# B4L_power.net
KiCad netlist of a schematic drawn in EAGLE
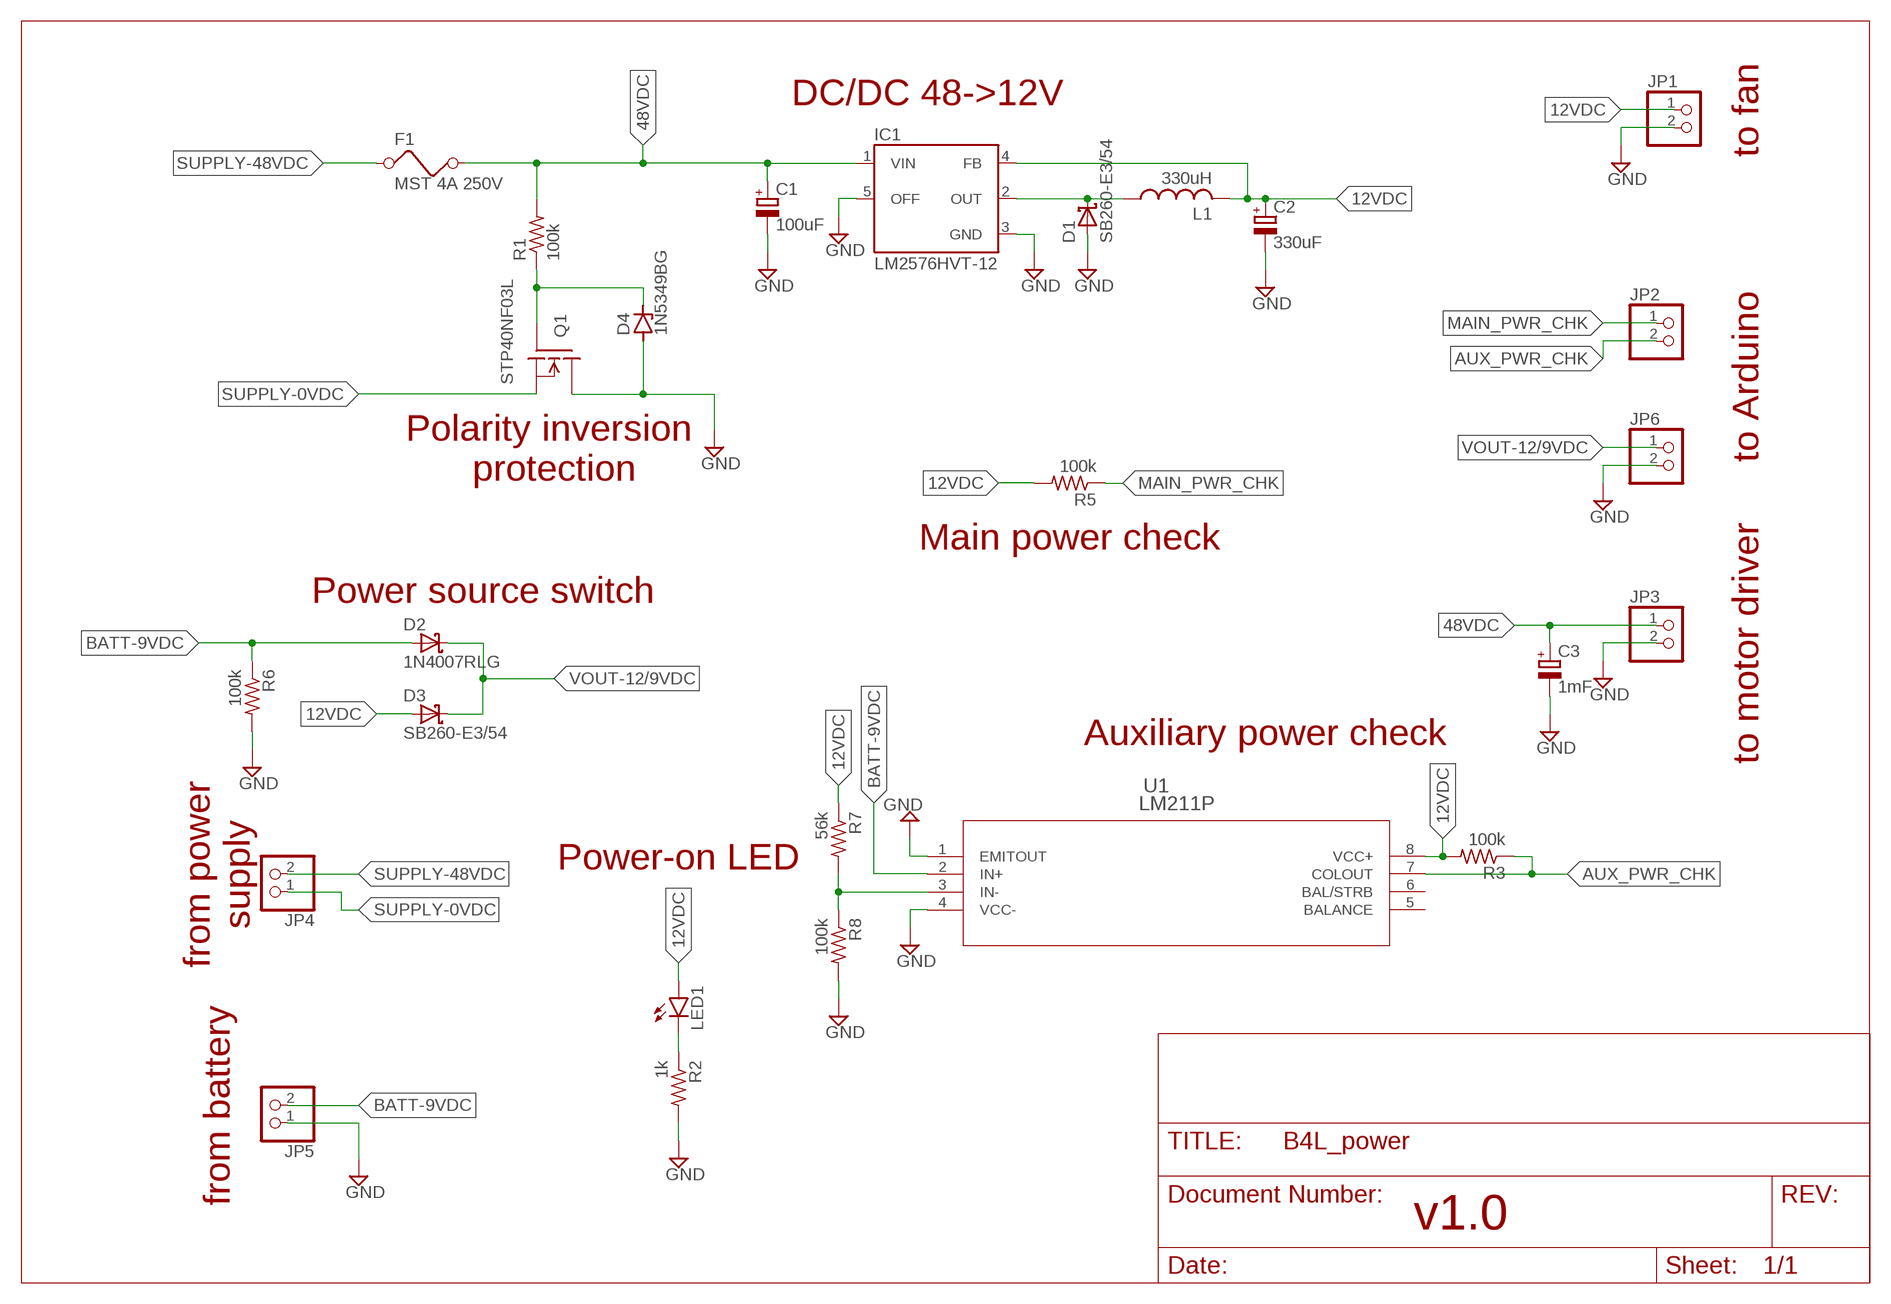
[diagram p0: schematic, sheet 1]

(export (version "E")
  (design (tool "Eeschema 10.0.6"))
  (components
    (comp (ref "C1")
      (value "100uF")
      (footprint "eagle-import:140CLH-1010")
      (libsource (lib "eagle-import") (part "CPOL-EU140CLH-1010"))
    )
    (comp (ref "C2")
      (value "330uF")
      (footprint "eagle-import:140CLH-1010")
      (libsource (lib "eagle-import") (part "CPOL-EU140CLH-1010"))
    )
    (comp (ref "C3")
      (value "1mF")
      (footprint "eagle-import:140CLH-1010")
      (libsource (lib "eagle-import") (part "CPOL-EU140CLH-1010"))
    )
    (comp (ref "D1")
      (value "SB260-E3/54")
      (footprint "eagle-import:DIOAD2120W130L950D530P")
      (fields (field (name "MF") "ON Semiconductor") (field (name "MP") "1N5822"))
      (libsource (lib "eagle-import") (part "1N5822"))
    )
    (comp (ref "D2")
      (value "1N4007RLG")
      (footprint "eagle-import:DIOAD2120W130L950D530P")
      (fields (field (name "MF") "ON Semiconductor") (field (name "MP") "1N5822"))
      (libsource (lib "eagle-import") (part "1N5822"))
    )
    (comp (ref "D3")
      (value "SB260-E3/54")
      (footprint "eagle-import:DIOAD2120W130L950D530P")
      (fields (field (name "MF") "ON Semiconductor") (field (name "MP") "1N5822"))
      (libsource (lib "eagle-import") (part "1N5822"))
    )
    (comp (ref "D4")
      (value "1N5349BG")
      (footprint "eagle-import:DO34Z7")
      (libsource (lib "eagle-import") (part "BZV10"))
    )
    (comp (ref "F1")
      (value "MST 4A 250V")
      (footprint "eagle-import:FUSE")
      (libsource (lib "eagle-import") (part "FUSE"))
    )
    (comp (ref "IC1")
      (value "LM2576HVT-12")
      (footprint "eagle-import:TO263-5")
      (libsource (lib "eagle-import") (part "LM2576S"))
    )
    (comp (ref "JP1")
      (value "PINHD-1X2")
      (footprint "eagle-import:1X02")
      (libsource (lib "eagle-import") (part "PINHD-1X2"))
    )
    (comp (ref "JP2")
      (value "PINHD-1X2")
      (footprint "eagle-import:1X02")
      (libsource (lib "eagle-import") (part "PINHD-1X2"))
    )
    (comp (ref "JP3")
      (value "PINHD-1X2")
      (footprint "eagle-import:1X02")
      (libsource (lib "eagle-import") (part "PINHD-1X2"))
    )
    (comp (ref "JP4")
      (value "PINHD-1X2")
      (footprint "eagle-import:1X02")
      (libsource (lib "eagle-import") (part "PINHD-1X2"))
    )
    (comp (ref "JP5")
      (value "PINHD-1X2")
      (footprint "eagle-import:1X02")
      (libsource (lib "eagle-import") (part "PINHD-1X2"))
    )
    (comp (ref "JP6")
      (value "PINHD-1X2")
      (footprint "eagle-import:1X02")
      (libsource (lib "eagle-import") (part "PINHD-1X2"))
    )
    (comp (ref "L1")
      (value "330uH")
      (footprint "eagle-import:IRF-1")
      (libsource (lib "eagle-import") (part "L-USIRF-1"))
    )
    (comp (ref "LED1")
      (value "LED5MM")
      (footprint "eagle-import:LED5MM")
      (libsource (lib "eagle-import") (part "LED5MM"))
    )
    (comp (ref "Q1")
      (value "STP40NF03L")
      (footprint "eagle-import:TO220")
      (libsource (lib "eagle-import") (part "BUZ10"))
    )
    (comp (ref "R1")
      (value "100k")
      (footprint "eagle-import:0309_10")
      (libsource (lib "eagle-import") (part "R-US_0309/10"))
    )
    (comp (ref "R2")
      (value "1k")
      (footprint "eagle-import:0309_10")
      (libsource (lib "eagle-import") (part "R-US_0309/10"))
    )
    (comp (ref "R3")
      (value "100k")
      (footprint "eagle-import:0309_10")
      (libsource (lib "eagle-import") (part "R-US_0309/10"))
    )
    (comp (ref "R5")
      (value "100k")
      (footprint "eagle-import:0309_10")
      (libsource (lib "eagle-import") (part "R-US_0309/10"))
    )
    (comp (ref "R6")
      (value "100k")
      (footprint "eagle-import:0309_10")
      (libsource (lib "eagle-import") (part "R-US_0309/10"))
    )
    (comp (ref "R7")
      (value "56k")
      (footprint "eagle-import:0309_10")
      (libsource (lib "eagle-import") (part "R-US_0309/10"))
    )
    (comp (ref "R8")
      (value "100k")
      (footprint "eagle-import:0309_10")
      (libsource (lib "eagle-import") (part "R-US_0309/10"))
    )
    (comp (ref "U1")
      (value "LM211P")
      (footprint "eagle-import:P8")
      (fields (field (name "GENERIC_PART_NUMBER") "LM211") (field (name "MANUFACTURER") "Texas Instruments"))
      (libsource (lib "eagle-import") (part "LM211P"))
    )
  )
  (nets
    (net (code "1") (name "12VDC") (class "Default")
      (node (ref "C2") (pin "+") (pinfunction "+_+") (pintype "passive"))
      (node (ref "D3") (pin "A") (pinfunction "A_A") (pintype "passive"))
      (node (ref "IC1") (pin "4") (pinfunction "FB_4") (pintype "input"))
      (node (ref "JP1") (pin "1") (pinfunction "1_1") (pintype "passive"))
      (node (ref "L1") (pin "2") (pinfunction "2_2") (pintype "passive"))
      (node (ref "LED1") (pin "A") (pinfunction "A_A") (pintype "passive"))
      (node (ref "R3") (pin "2") (pinfunction "2_2") (pintype "passive"))
      (node (ref "R5") (pin "2") (pinfunction "2_2") (pintype "passive"))
      (node (ref "R7") (pin "1") (pinfunction "1_1") (pintype "passive"))
      (node (ref "U1") (pin "8") (pinfunction "VCC+_8") (pintype "power_in"))
    )
    (net (code "2") (name "48VDC") (class "Default")
      (node (ref "C1") (pin "+") (pinfunction "+_+") (pintype "passive"))
      (node (ref "C3") (pin "+") (pinfunction "+_+") (pintype "passive"))
      (node (ref "F1") (pin "2") (pinfunction "2_2") (pintype "passive"))
      (node (ref "IC1") (pin "1") (pinfunction "VIN_1") (pintype "power_in"))
      (node (ref "JP3") (pin "1") (pinfunction "1_1") (pintype "passive"))
      (node (ref "R1") (pin "2") (pinfunction "2_2") (pintype "passive"))
    )
    (net (code "3") (name "AUX_PWR_CHK") (class "Default")
      (node (ref "JP2") (pin "2") (pinfunction "2_2") (pintype "passive"))
      (node (ref "R3") (pin "1") (pinfunction "1_1") (pintype "passive"))
      (node (ref "U1") (pin "7") (pinfunction "COLOUT_7") (pintype "output"))
    )
    (net (code "4") (name "BATT-9VDC") (class "Default")
      (node (ref "D2") (pin "A") (pinfunction "A_A") (pintype "passive"))
      (node (ref "JP5") (pin "2") (pinfunction "2_2") (pintype "passive"))
      (node (ref "R6") (pin "1") (pinfunction "1_1") (pintype "passive"))
      (node (ref "U1") (pin "2") (pinfunction "IN+_2") (pintype "input"))
    )
    (net (code "5") (name "GND") (class "Default")
      (node (ref "C1") (pin "-") (pinfunction "-_-") (pintype "passive"))
      (node (ref "C2") (pin "-") (pinfunction "-_-") (pintype "passive"))
      (node (ref "C3") (pin "-") (pinfunction "-_-") (pintype "passive"))
      (node (ref "D1") (pin "A") (pinfunction "A_A") (pintype "passive"))
      (node (ref "D4") (pin "A") (pinfunction "A_A") (pintype "passive"))
      (node (ref "IC1") (pin "3") (pinfunction "GND_3") (pintype "power_in"))
      (node (ref "IC1") (pin "5") (pinfunction "OFF_5") (pintype "input"))
      (node (ref "JP1") (pin "2") (pinfunction "2_2") (pintype "passive"))
      (node (ref "JP3") (pin "2") (pinfunction "2_2") (pintype "passive"))
      (node (ref "JP5") (pin "1") (pinfunction "1_1") (pintype "passive"))
      (node (ref "JP6") (pin "2") (pinfunction "2_2") (pintype "passive"))
      (node (ref "Q1") (pin "2") (pinfunction "D_2") (pintype "passive"))
      (node (ref "R2") (pin "2") (pinfunction "2_2") (pintype "passive"))
      (node (ref "R6") (pin "2") (pinfunction "2_2") (pintype "passive"))
      (node (ref "R8") (pin "2") (pinfunction "2_2") (pintype "passive"))
      (node (ref "U1") (pin "1") (pinfunction "EMITOUT_1") (pintype "output"))
      (node (ref "U1") (pin "4") (pinfunction "VCC-_4") (pintype "power_in"))
    )
    (net (code "6") (name "MAIN_PWR_CHK") (class "Default")
      (node (ref "JP2") (pin "1") (pinfunction "1_1") (pintype "passive"))
      (node (ref "R5") (pin "1") (pinfunction "1_1") (pintype "passive"))
    )
    (net (code "7") (name "Net-(IC1-OUT)") (class "Default")
      (node (ref "D1") (pin "C") (pinfunction "C_C") (pintype "passive"))
      (node (ref "IC1") (pin "2") (pinfunction "OUT_2") (pintype "output"))
      (node (ref "L1") (pin "1") (pinfunction "1_1") (pintype "passive"))
    )
    (net (code "8") (name "Net-(LED1-C)") (class "Default")
      (node (ref "LED1") (pin "K") (pinfunction "C_K") (pintype "passive"))
      (node (ref "R2") (pin "1") (pinfunction "1_1") (pintype "passive"))
    )
    (net (code "9") (name "Net-(Q1-G)") (class "Default")
      (node (ref "D4") (pin "C") (pinfunction "C_C") (pintype "passive"))
      (node (ref "Q1") (pin "1") (pinfunction "G_1") (pintype "passive"))
      (node (ref "R1") (pin "1") (pinfunction "1_1") (pintype "passive"))
    )
    (net (code "10") (name "Net-(U1-IN-)") (class "Default")
      (node (ref "R7") (pin "2") (pinfunction "2_2") (pintype "passive"))
      (node (ref "R8") (pin "1") (pinfunction "1_1") (pintype "passive"))
      (node (ref "U1") (pin "3") (pinfunction "IN-_3") (pintype "input"))
    )
    (net (code "11") (name "SUPPLY-0VDC") (class "Default")
      (node (ref "JP4") (pin "1") (pinfunction "1_1") (pintype "passive"))
      (node (ref "Q1") (pin "3") (pinfunction "S_3") (pintype "passive"))
    )
    (net (code "12") (name "SUPPLY-48VDC") (class "Default")
      (node (ref "F1") (pin "1") (pinfunction "1_1") (pintype "passive"))
      (node (ref "JP4") (pin "2") (pinfunction "2_2") (pintype "passive"))
    )
    (net (code "13") (name "VOUT-12{slash}9VDC") (class "Default")
      (node (ref "D2") (pin "C") (pinfunction "C_C") (pintype "passive"))
      (node (ref "D3") (pin "C") (pinfunction "C_C") (pintype "passive"))
      (node (ref "JP6") (pin "1") (pinfunction "1_1") (pintype "passive"))
    )
    (net (code "14") (name "unconnected-(U1-BALANCE-Pad5)") (class "Default")
      (node (ref "U1") (pin "5") (pinfunction "BALANCE_5") (pintype "passive"))
    )
    (net (code "15") (name "unconnected-(U1-BAL{slash}STRB-Pad6)") (class "Default")
      (node (ref "U1") (pin "6") (pinfunction "BAL/STRB_6") (pintype "passive"))
    )
  )
)
